# filaSens.net
KiCad netlist of a schematic drawn in EAGLE
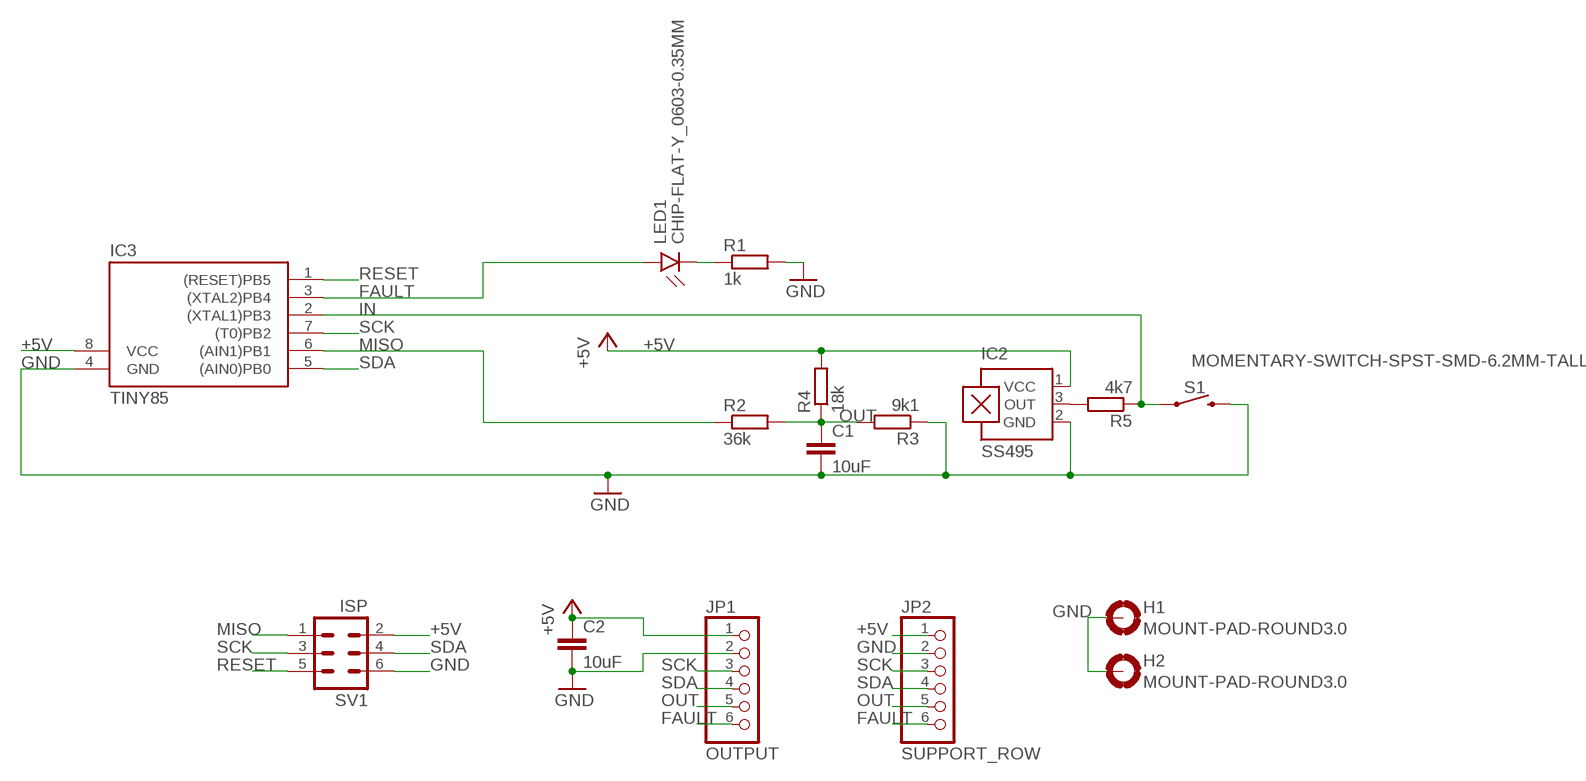
[diagram p0: schematic, sheet 1]

(export (version "E")
  (design (tool "Eeschema 10.0.6"))
  (components
    (comp (ref "C1")
      (value "10uF")
      (footprint "eagle-import:C0402")
      (libsource (lib "eagle-import") (part "C-EUC0402"))
    )
    (comp (ref "C2")
      (value "10uF")
      (footprint "eagle-import:C0402")
      (libsource (lib "eagle-import") (part "C-EUC0402"))
    )
    (comp (ref "H1")
      (value "MOUNT-PAD-ROUND3.0")
      (footprint "eagle-import:3,0-PAD")
      (libsource (lib "eagle-import") (part "MOUNT-PAD-ROUND3.0"))
    )
    (comp (ref "H2")
      (value "MOUNT-PAD-ROUND3.0")
      (footprint "eagle-import:3,0-PAD")
      (libsource (lib "eagle-import") (part "MOUNT-PAD-ROUND3.0"))
    )
    (comp (ref "IC2")
      (value "SS495")
      (footprint "eagle-import:SIP3-UA")
      (fields (field (name "MF") "ALLEGRO MICROSYSTEMS, INC.") (field (name "MPN") "A1302EUA-T"))
      (libsource (lib "eagle-import") (part "A13?UA02"))
    )
    (comp (ref "IC3")
      (value "TINY85")
      (footprint "eagle-import:SOIC8")
      (libsource (lib "eagle-import") (part "TINY10S"))
    )
    (comp (ref "JP1")
      (value "OUTPUT")
      (footprint "eagle-import:1X06")
      (libsource (lib "eagle-import") (part "PINHD-1X6"))
    )
    (comp (ref "JP2")
      (value "SUPPORT_ROW")
      (footprint "eagle-import:1X06")
      (libsource (lib "eagle-import") (part "PINHD-1X6"))
    )
    (comp (ref "LED1")
      (value "CHIP-FLAT-Y_0603-0.35MM")
      (footprint "eagle-import:LEDC1608X35N_FLAT-Y")
      (libsource (lib "eagle-import") (part "CHIP-FLAT-Y_0603-0.35MM"))
    )
    (comp (ref "R1")
      (value "1k")
      (footprint "eagle-import:R0402")
      (libsource (lib "eagle-import") (part "R-EU_R0402"))
    )
    (comp (ref "R2")
      (value "36k")
      (footprint "eagle-import:R0402")
      (libsource (lib "eagle-import") (part "R-EU_R0402"))
    )
    (comp (ref "R3")
      (value "9k1")
      (footprint "eagle-import:R0402")
      (libsource (lib "eagle-import") (part "R-EU_R0402"))
    )
    (comp (ref "R4")
      (value "18k")
      (footprint "eagle-import:R0402")
      (libsource (lib "eagle-import") (part "R-EU_R0402"))
    )
    (comp (ref "R5")
      (value "4k7")
      (footprint "eagle-import:R0402")
      (libsource (lib "eagle-import") (part "R-EU_R0402"))
    )
    (comp (ref "S1")
      (value "MOMENTARY-SWITCH-SPST-SMD-6.2MM-TALL")
      (footprint "eagle-import:TACTILE_SWITCH_SMD_6.2MM_TALL")
      (libsource (lib "eagle-import") (part "MOMENTARY-SWITCH-SPST-SMD-6.2MM-TALL"))
    )
    (comp (ref "SV1")
      (value "ISP")
      (footprint "eagle-import:MA03-2")
      (libsource (lib "eagle-import") (part "MA03-2"))
    )
  )
  (nets
    (net (code "1") (name "+5V") (class "Default")
      (node (ref "C2") (pin "1") (pinfunction "1_1") (pintype "passive"))
      (node (ref "IC2") (pin "1") (pinfunction "VCC_1") (pintype "power_in"))
      (node (ref "IC3") (pin "8") (pinfunction "VCC_8") (pintype "power_in"))
      (node (ref "JP1") (pin "1") (pinfunction "1_1") (pintype "passive"))
      (node (ref "JP2") (pin "1") (pinfunction "1_1") (pintype "passive"))
      (node (ref "R4") (pin "2") (pinfunction "2_2") (pintype "passive"))
      (node (ref "SV1") (pin "2") (pinfunction "2_2") (pintype "passive"))
    )
    (net (code "2") (name "/FAULT") (class "Default")
      (node (ref "IC3") (pin "3") (pinfunction "(XTAL2)PB4_3") (pintype "bidirectional"))
      (node (ref "JP1") (pin "6") (pinfunction "6_6") (pintype "passive"))
      (node (ref "JP2") (pin "6") (pinfunction "6_6") (pintype "passive"))
      (node (ref "LED1") (pin "A") (pinfunction "A_A") (pintype "passive"))
    )
    (net (code "3") (name "/IN") (class "Default")
      (node (ref "IC3") (pin "2") (pinfunction "(XTAL1)PB3_2") (pintype "bidirectional"))
      (node (ref "R5") (pin "1") (pinfunction "1_1") (pintype "passive"))
      (node (ref "S1") (pin "A2") (pinfunction "1_A2") (pintype "passive"))
    )
    (net (code "4") (name "/MISO") (class "Default")
      (node (ref "IC3") (pin "6") (pinfunction "(AIN1)PB1_6") (pintype "bidirectional"))
      (node (ref "R2") (pin "1") (pinfunction "1_1") (pintype "passive"))
      (node (ref "SV1") (pin "1") (pinfunction "1_1") (pintype "passive"))
    )
    (net (code "5") (name "/OUT") (class "Default")
      (node (ref "C1") (pin "1") (pinfunction "1_1") (pintype "passive"))
      (node (ref "JP1") (pin "5") (pinfunction "5_5") (pintype "passive"))
      (node (ref "JP2") (pin "5") (pinfunction "5_5") (pintype "passive"))
      (node (ref "R2") (pin "2") (pinfunction "2_2") (pintype "passive"))
      (node (ref "R3") (pin "2") (pinfunction "2_2") (pintype "passive"))
      (node (ref "R4") (pin "1") (pinfunction "1_1") (pintype "passive"))
    )
    (net (code "6") (name "/RESET") (class "Default")
      (node (ref "IC3") (pin "1") (pinfunction "(RESET)PB5_1") (pintype "bidirectional"))
      (node (ref "SV1") (pin "5") (pinfunction "5_5") (pintype "passive"))
    )
    (net (code "7") (name "/SCK") (class "Default")
      (node (ref "IC3") (pin "7") (pinfunction "(T0)PB2_7") (pintype "bidirectional"))
      (node (ref "JP1") (pin "3") (pinfunction "3_3") (pintype "passive"))
      (node (ref "JP2") (pin "3") (pinfunction "3_3") (pintype "passive"))
      (node (ref "SV1") (pin "3") (pinfunction "3_3") (pintype "passive"))
    )
    (net (code "8") (name "/SDA") (class "Default")
      (node (ref "IC3") (pin "5") (pinfunction "(AIN0)PB0_5") (pintype "bidirectional"))
      (node (ref "JP1") (pin "4") (pinfunction "4_4") (pintype "passive"))
      (node (ref "JP2") (pin "4") (pinfunction "4_4") (pintype "passive"))
      (node (ref "SV1") (pin "4") (pinfunction "4_4") (pintype "passive"))
    )
    (net (code "9") (name "GND") (class "Default")
      (node (ref "C1") (pin "2") (pinfunction "2_2") (pintype "passive"))
      (node (ref "C2") (pin "2") (pinfunction "2_2") (pintype "passive"))
      (node (ref "H1") (pin "B3,0") (pinfunction "MOUNT_B3,0") (pintype "passive"))
      (node (ref "H2") (pin "B3,0") (pinfunction "MOUNT_B3,0") (pintype "passive"))
      (node (ref "IC2") (pin "2") (pinfunction "GND_2") (pintype "power_in"))
      (node (ref "IC3") (pin "4") (pinfunction "GND_4") (pintype "power_in"))
      (node (ref "JP1") (pin "2") (pinfunction "2_2") (pintype "passive"))
      (node (ref "JP2") (pin "2") (pinfunction "2_2") (pintype "passive"))
      (node (ref "R1") (pin "2") (pinfunction "2_2") (pintype "passive"))
      (node (ref "R3") (pin "1") (pinfunction "1_1") (pintype "passive"))
      (node (ref "S1") (pin "B2") (pinfunction "2_B2") (pintype "passive"))
      (node (ref "SV1") (pin "6") (pinfunction "6_6") (pintype "passive"))
    )
    (net (code "10") (name "Net-(IC2-OUT)") (class "Default")
      (node (ref "IC2") (pin "3") (pinfunction "OUT_3") (pintype "output"))
      (node (ref "R5") (pin "2") (pinfunction "2_2") (pintype "passive"))
    )
    (net (code "11") (name "Net-(LED1-PadC)") (class "Default")
      (node (ref "LED1") (pin "C") (pinfunction "C_C") (pintype "passive"))
      (node (ref "R1") (pin "1") (pinfunction "1_1") (pintype "passive"))
    )
  )
)
